# RotorPSU.net
KiCad netlist of a schematic drawn in EAGLE
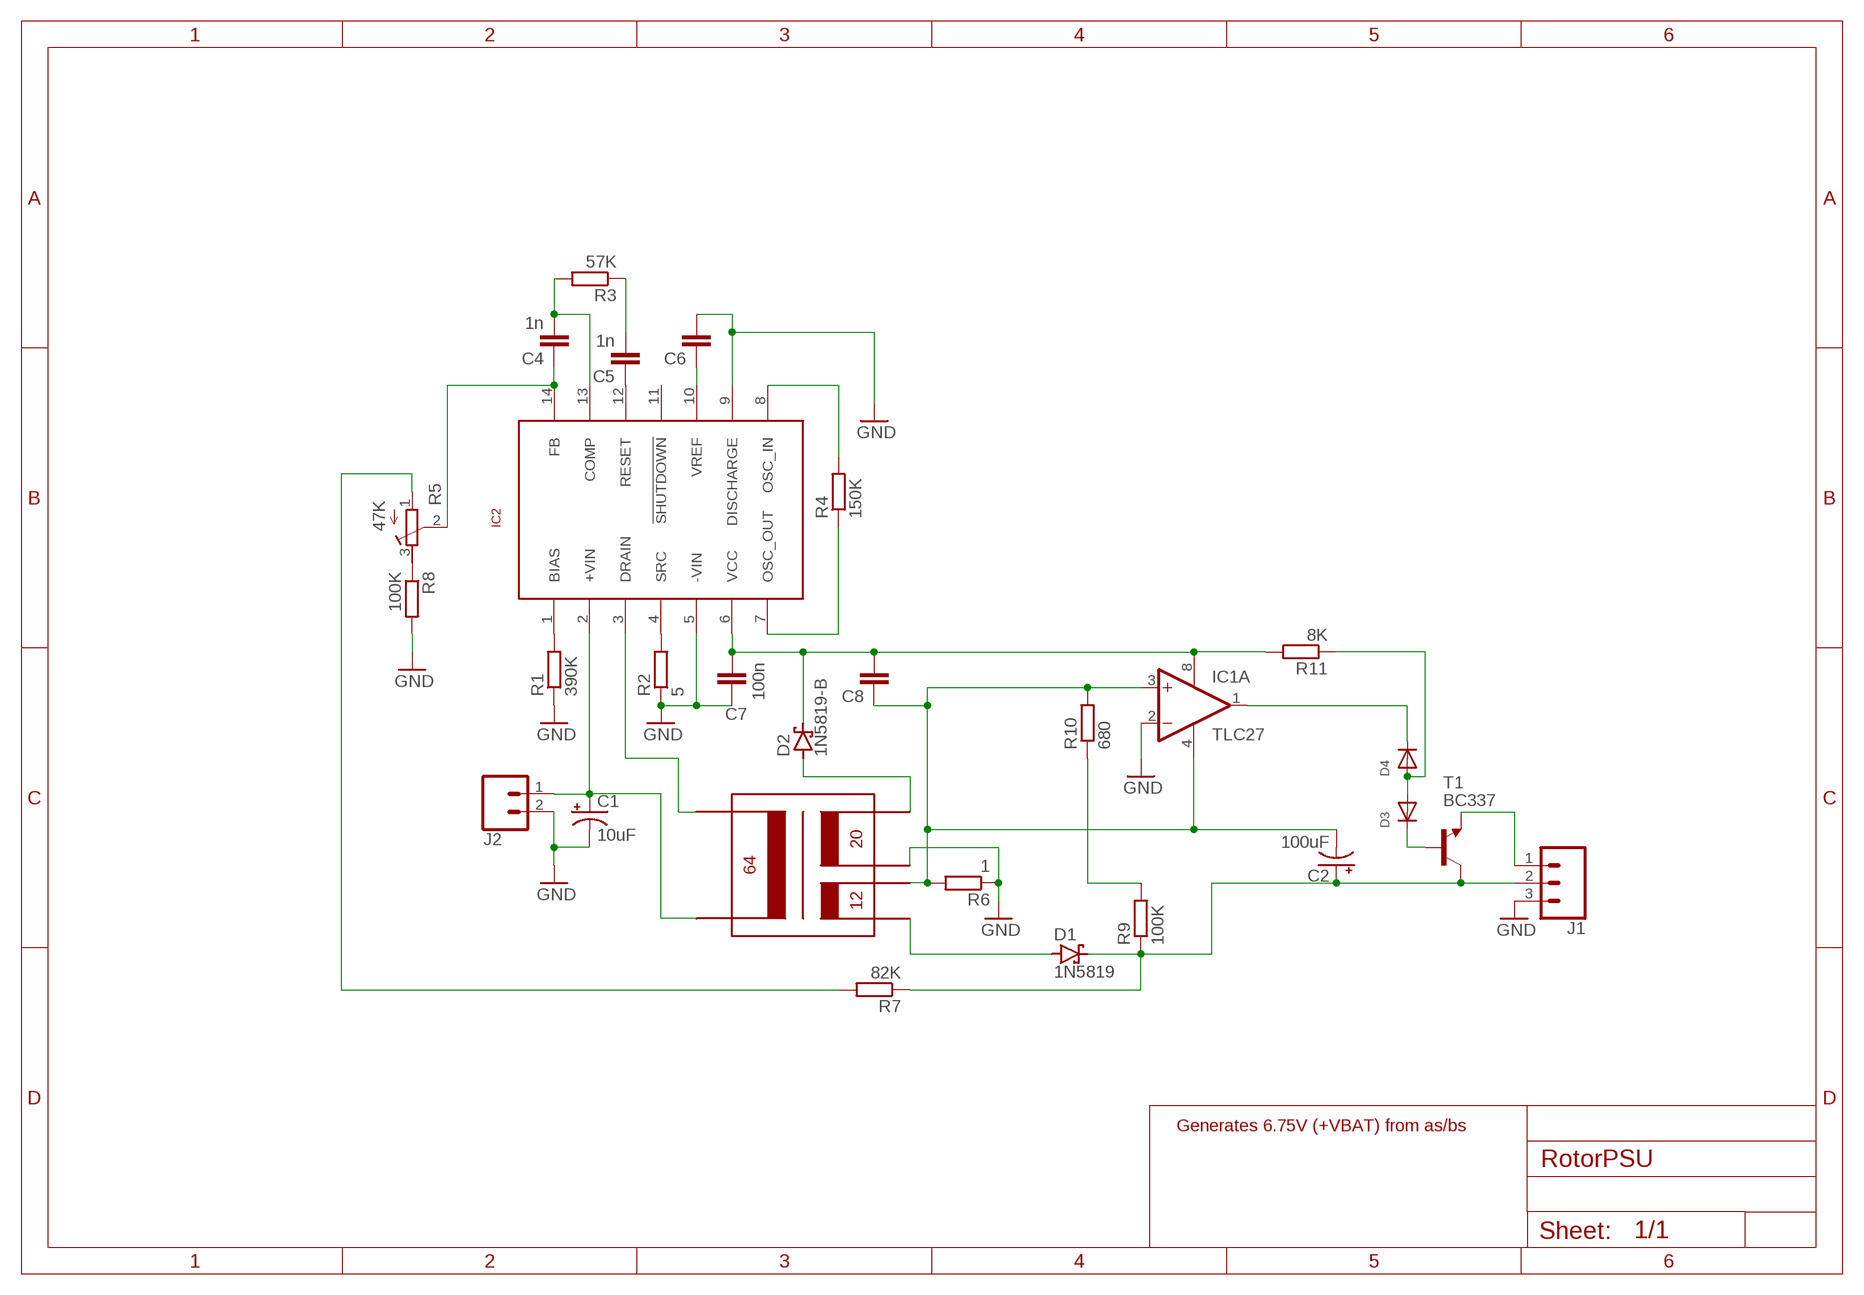
[diagram p0: schematic, sheet 1]

(export (version "E")
  (design (tool "Eeschema 10.0.6"))
  (components
    (comp (ref "C1")
      (value "10uF")
      (footprint "eagle-import:CPOL-RADIAL-2.5MM-5MM")
      (libsource (lib "eagle-import") (part "10UF-POLAR-RADIAL-2.5MM-25V-20%"))
    )
    (comp (ref "C2")
      (value "100uF")
      (footprint "eagle-import:CPOL-RADIAL-2.5MM-6.5MM")
      (libsource (lib "eagle-import") (part "100UF-POLAR-RADIAL-2.5MM-25V-20%"))
    )
    (comp (ref "C4")
      (value "1n")
      (footprint "eagle-import:C025-025X050")
      (libsource (lib "eagle-import") (part "C-EU025-025X050"))
    )
    (comp (ref "C5")
      (value "1n")
      (footprint "eagle-import:C025-025X050")
      (libsource (lib "eagle-import") (part "C-EU025-025X050"))
    )
    (comp (ref "C6")
      (value "C-EU025-025X050")
      (footprint "eagle-import:C025-025X050")
      (libsource (lib "eagle-import") (part "C-EU025-025X050"))
    )
    (comp (ref "C7")
      (value "100n")
      (footprint "eagle-import:C025-025X050")
      (libsource (lib "eagle-import") (part "C-EU025-025X050"))
    )
    (comp (ref "C8")
      (value "C-EU025-025X050")
      (footprint "eagle-import:C025-025X050")
      (libsource (lib "eagle-import") (part "C-EU025-025X050"))
    )
    (comp (ref "D1")
      (value "1N5819")
      (footprint "eagle-import:DO41-7.6")
      (libsource (lib "eagle-import") (part "1N5819-B"))
    )
    (comp (ref "D2")
      (value "1N5819-B")
      (footprint "eagle-import:DO41-7.6")
      (libsource (lib "eagle-import") (part "1N5819-B"))
    )
    (comp (ref "D3")
      (value "DIODEDO-1N4148")
      (footprint "eagle-import:DO-1N4148")
      (libsource (lib "eagle-import") (part "DIODEDO-1N4148"))
    )
    (comp (ref "D4")
      (value "DIODEDO-1N4148")
      (footprint "eagle-import:DO-1N4148")
      (libsource (lib "eagle-import") (part "DIODEDO-1N4148"))
    )
    (comp (ref "IC1")
      (value "TLC27")
      (footprint "eagle-import:DIL08")
      (libsource (lib "eagle-import") (part "TLC27LP2AC"))
    )
    (comp (ref "IC2")
      (value "SI9100")
      (footprint "eagle-import:DIL14")
      (libsource (lib "eagle-import") (part "SI9100"))
    )
    (comp (ref "J1")
      (value "CONN_03")
      (footprint "eagle-import:1X03")
      (libsource (lib "eagle-import") (part "CONN_03"))
    )
    (comp (ref "J2")
      (value "CONN_02")
      (footprint "eagle-import:1X02")
      (libsource (lib "eagle-import") (part "CONN_02"))
    )
    (comp (ref "R1")
      (value "390K")
      (footprint "eagle-import:0207_7")
      (libsource (lib "eagle-import") (part "R-EU_0207/7"))
    )
    (comp (ref "R2")
      (value "5")
      (footprint "eagle-import:0207_7")
      (libsource (lib "eagle-import") (part "R-EU_0207/7"))
    )
    (comp (ref "R3")
      (value "57K")
      (footprint "eagle-import:0207_7")
      (libsource (lib "eagle-import") (part "R-EU_0207/7"))
    )
    (comp (ref "R4")
      (value "150K")
      (footprint "eagle-import:0207_7")
      (libsource (lib "eagle-import") (part "R-EU_0207/7"))
    )
    (comp (ref "R5")
      (value "47K")
      (footprint "eagle-import:RTRIM3296W")
      (libsource (lib "eagle-import") (part "R-TRIMM3296W"))
    )
    (comp (ref "R6")
      (value "1")
      (footprint "eagle-import:0207_7")
      (libsource (lib "eagle-import") (part "R-EU_0207/7"))
    )
    (comp (ref "R7")
      (value "82K")
      (footprint "eagle-import:0207_7")
      (libsource (lib "eagle-import") (part "R-EU_0207/7"))
    )
    (comp (ref "R8")
      (value "100K")
      (footprint "eagle-import:0207_7")
      (libsource (lib "eagle-import") (part "R-EU_0207/7"))
    )
    (comp (ref "R9")
      (value "100K")
      (footprint "eagle-import:0207_7")
      (libsource (lib "eagle-import") (part "R-EU_0207/7"))
    )
    (comp (ref "R10")
      (value "680")
      (footprint "eagle-import:0207_7")
      (libsource (lib "eagle-import") (part "R-EU_0207/7"))
    )
    (comp (ref "R11")
      (value "8K")
      (footprint "eagle-import:0207_7")
      (libsource (lib "eagle-import") (part "R-EU_0207/7"))
    )
    (comp (ref "T1")
      (value "BC337")
      (footprint "eagle-import:TO92")
      (libsource (lib "eagle-import") (part "BC337"))
    )
    (comp (ref "TR1")
      (value "ROTOR_XFORMER")
      (footprint "eagle-import:ROTOR_XFORMER")
      (libsource (lib "eagle-import") (part "ROTOR_XFORMER"))
    )
  )
  (nets
    (net (code "1") (name "GND") (class "Default")
      (node (ref "C1") (pin "2") (pinfunction "-_2") (pintype "passive"))
      (node (ref "C6") (pin "2") (pinfunction "2_2") (pintype "passive"))
      (node (ref "C7") (pin "1") (pinfunction "1_1") (pintype "passive"))
      (node (ref "IC1") (pin "2") (pinfunction "-IN_2") (pintype "input"))
      (node (ref "IC2") (pin "5") (pinfunction "-VIN_5") (pintype "power_in"))
      (node (ref "IC2") (pin "9") (pinfunction "DISCHARGE_9") (pintype "bidirectional"))
      (node (ref "J1") (pin "3") (pinfunction "3_3") (pintype "passive"))
      (node (ref "J2") (pin "2") (pinfunction "2_2") (pintype "passive"))
      (node (ref "R1") (pin "1") (pinfunction "1_1") (pintype "passive"))
      (node (ref "R2") (pin "1") (pinfunction "1_1") (pintype "passive"))
      (node (ref "R6") (pin "1") (pinfunction "1_1") (pintype "passive"))
      (node (ref "R8") (pin "2") (pinfunction "2_2") (pintype "passive"))
      (node (ref "TR1") (pin "P$8") (pinfunction "20A_P$8") (pintype "bidirectional"))
    )
    (net (code "2") (name "Net-(C1-+)") (class "Default")
      (node (ref "C1") (pin "1") (pinfunction "+_1") (pintype "passive"))
      (node (ref "IC2") (pin "2") (pinfunction "+VIN_2") (pintype "power_in"))
      (node (ref "J2") (pin "1") (pinfunction "1_1") (pintype "passive"))
      (node (ref "TR1") (pin "P$2") (pinfunction "64A_P$2") (pintype "bidirectional"))
    )
    (net (code "3") (name "Net-(C2-+)") (class "Default")
      (node (ref "C2") (pin "1") (pinfunction "+_1") (pintype "passive"))
      (node (ref "D1") (pin "C") (pinfunction "C_C") (pintype "passive"))
      (node (ref "J1") (pin "2") (pinfunction "2_2") (pintype "passive"))
      (node (ref "R7") (pin "1") (pinfunction "1_1") (pintype "passive"))
      (node (ref "R9") (pin "1") (pinfunction "1_1") (pintype "passive"))
      (node (ref "T1") (pin "3") (pinfunction "C_3") (pintype "passive"))
    )
    (net (code "4") (name "Net-(C2--)") (class "Default")
      (node (ref "C2") (pin "2") (pinfunction "-_2") (pintype "passive"))
      (node (ref "C8") (pin "1") (pinfunction "1_1") (pintype "passive"))
      (node (ref "IC1") (pin "3") (pinfunction "+IN_3") (pintype "input"))
      (node (ref "IC1") (pin "4") (pinfunction "GND_4") (pintype "power_in"))
      (node (ref "R10") (pin "2") (pinfunction "2_2") (pintype "passive"))
      (node (ref "R6") (pin "2") (pinfunction "2_2") (pintype "passive"))
      (node (ref "TR1") (pin "P$7") (pinfunction "12B_P$7") (pintype "bidirectional"))
    )
    (net (code "5") (name "Net-(C5-Pad2)") (class "Default")
      (node (ref "C5") (pin "2") (pinfunction "2_2") (pintype "passive"))
      (node (ref "R3") (pin "1") (pinfunction "1_1") (pintype "passive"))
    )
    (net (code "6") (name "Net-(D3-PadA)") (class "Default")
      (node (ref "D3") (pin "A") (pinfunction "A_A") (pintype "passive"))
      (node (ref "D4") (pin "A") (pinfunction "A_A") (pintype "passive"))
      (node (ref "R11") (pin "1") (pinfunction "1_1") (pintype "passive"))
    )
    (net (code "7") (name "Net-(IC1A-OUT)") (class "Default")
      (node (ref "D4") (pin "C") (pinfunction "C_C") (pintype "passive"))
      (node (ref "IC1") (pin "1") (pinfunction "OUT_1") (pintype "output"))
    )
    (net (code "8") (name "Net-(IC1C-VDD)") (class "Default")
      (node (ref "C7") (pin "2") (pinfunction "2_2") (pintype "passive"))
      (node (ref "C8") (pin "2") (pinfunction "2_2") (pintype "passive"))
      (node (ref "D2") (pin "C") (pinfunction "C_C") (pintype "passive"))
      (node (ref "IC1") (pin "8") (pinfunction "VDD_8") (pintype "power_in"))
      (node (ref "IC2") (pin "6") (pinfunction "VCC_6") (pintype "power_in"))
      (node (ref "R11") (pin "2") (pinfunction "2_2") (pintype "passive"))
    )
    (net (code "9") (name "Net-(IC2-BIAS)") (class "Default")
      (node (ref "IC2") (pin "1") (pinfunction "BIAS_1") (pintype "bidirectional"))
      (node (ref "R1") (pin "2") (pinfunction "2_2") (pintype "passive"))
    )
    (net (code "10") (name "Net-(IC2-COMP)") (class "Default")
      (node (ref "C4") (pin "2") (pinfunction "2_2") (pintype "passive"))
      (node (ref "IC2") (pin "13") (pinfunction "COMP_13") (pintype "bidirectional"))
      (node (ref "R3") (pin "2") (pinfunction "2_2") (pintype "passive"))
    )
    (net (code "11") (name "Net-(IC2-DRAIN)") (class "Default")
      (node (ref "IC2") (pin "3") (pinfunction "DRAIN_3") (pintype "power_in"))
      (node (ref "TR1") (pin "P$4") (pinfunction "64B_P$4") (pintype "bidirectional"))
    )
    (net (code "12") (name "Net-(IC2-FB)") (class "Default")
      (node (ref "C4") (pin "1") (pinfunction "1_1") (pintype "passive"))
      (node (ref "IC2") (pin "14") (pinfunction "FB_14") (pintype "bidirectional"))
      (node (ref "R5") (pin "2") (pinfunction "S_2") (pintype "passive"))
    )
    (net (code "13") (name "Net-(IC2-OSC_IN)") (class "Default")
      (node (ref "IC2") (pin "8") (pinfunction "OSC_IN_8") (pintype "input"))
      (node (ref "R4") (pin "2") (pinfunction "2_2") (pintype "passive"))
    )
    (net (code "14") (name "Net-(IC2-OSC_OUT)") (class "Default")
      (node (ref "IC2") (pin "7") (pinfunction "OSC_OUT_7") (pintype "output"))
      (node (ref "R4") (pin "1") (pinfunction "1_1") (pintype "passive"))
    )
    (net (code "15") (name "Net-(IC2-RESET)") (class "Default")
      (node (ref "C5") (pin "1") (pinfunction "1_1") (pintype "passive"))
      (node (ref "IC2") (pin "12") (pinfunction "RESET_12") (pintype "input"))
    )
    (net (code "16") (name "Net-(IC2-SRC)") (class "Default")
      (node (ref "IC2") (pin "4") (pinfunction "SRC_4") (pintype "power_in"))
      (node (ref "R2") (pin "2") (pinfunction "2_2") (pintype "passive"))
    )
    (net (code "17") (name "Net-(IC2-VREF)") (class "Default")
      (node (ref "C6") (pin "1") (pinfunction "1_1") (pintype "passive"))
      (node (ref "IC2") (pin "10") (pinfunction "VREF_10") (pintype "bidirectional"))
    )
    (net (code "18") (name "Net-(R5-A)") (class "Default")
      (node (ref "R5") (pin "1") (pinfunction "A_1") (pintype "passive"))
      (node (ref "R7") (pin "2") (pinfunction "2_2") (pintype "passive"))
    )
    (net (code "19") (name "Net-(R5-E)") (class "Default")
      (node (ref "R5") (pin "3") (pinfunction "E_3") (pintype "passive"))
      (node (ref "R8") (pin "1") (pinfunction "1_1") (pintype "passive"))
    )
    (net (code "20") (name "Net-(R10-Pad1)") (class "Default")
      (node (ref "R10") (pin "1") (pinfunction "1_1") (pintype "passive"))
      (node (ref "R9") (pin "2") (pinfunction "2_2") (pintype "passive"))
    )
    (net (code "21") (name "Net-(T1-B)") (class "Default")
      (node (ref "D3") (pin "C") (pinfunction "C_C") (pintype "passive"))
      (node (ref "T1") (pin "2") (pinfunction "B_2") (pintype "passive"))
    )
    (net (code "22") (name "Net-(T1-E)") (class "Default")
      (node (ref "J1") (pin "1") (pinfunction "1_1") (pintype "passive"))
      (node (ref "T1") (pin "1") (pinfunction "E_1") (pintype "passive"))
    )
    (net (code "23") (name "Net-(TR1-12A)") (class "Default")
      (node (ref "D1") (pin "A") (pinfunction "A_A") (pintype "passive"))
      (node (ref "TR1") (pin "P$6") (pinfunction "12A_P$6") (pintype "bidirectional"))
    )
    (net (code "24") (name "Net-(TR1-20B)") (class "Default")
      (node (ref "D2") (pin "A") (pinfunction "A_A") (pintype "passive"))
      (node (ref "TR1") (pin "P$3") (pinfunction "20B_P$3") (pintype "bidirectional"))
    )
    (net (code "25") (name "unconnected-(IC2-~{SHUTDOWN}-Pad11)") (class "Default")
      (node (ref "IC2") (pin "11") (pinfunction "~{SHUTDOWN}_11") (pintype "input"))
    )
  )
)
